# touche_server.net
KiCad netlist of a schematic drawn in EAGLE
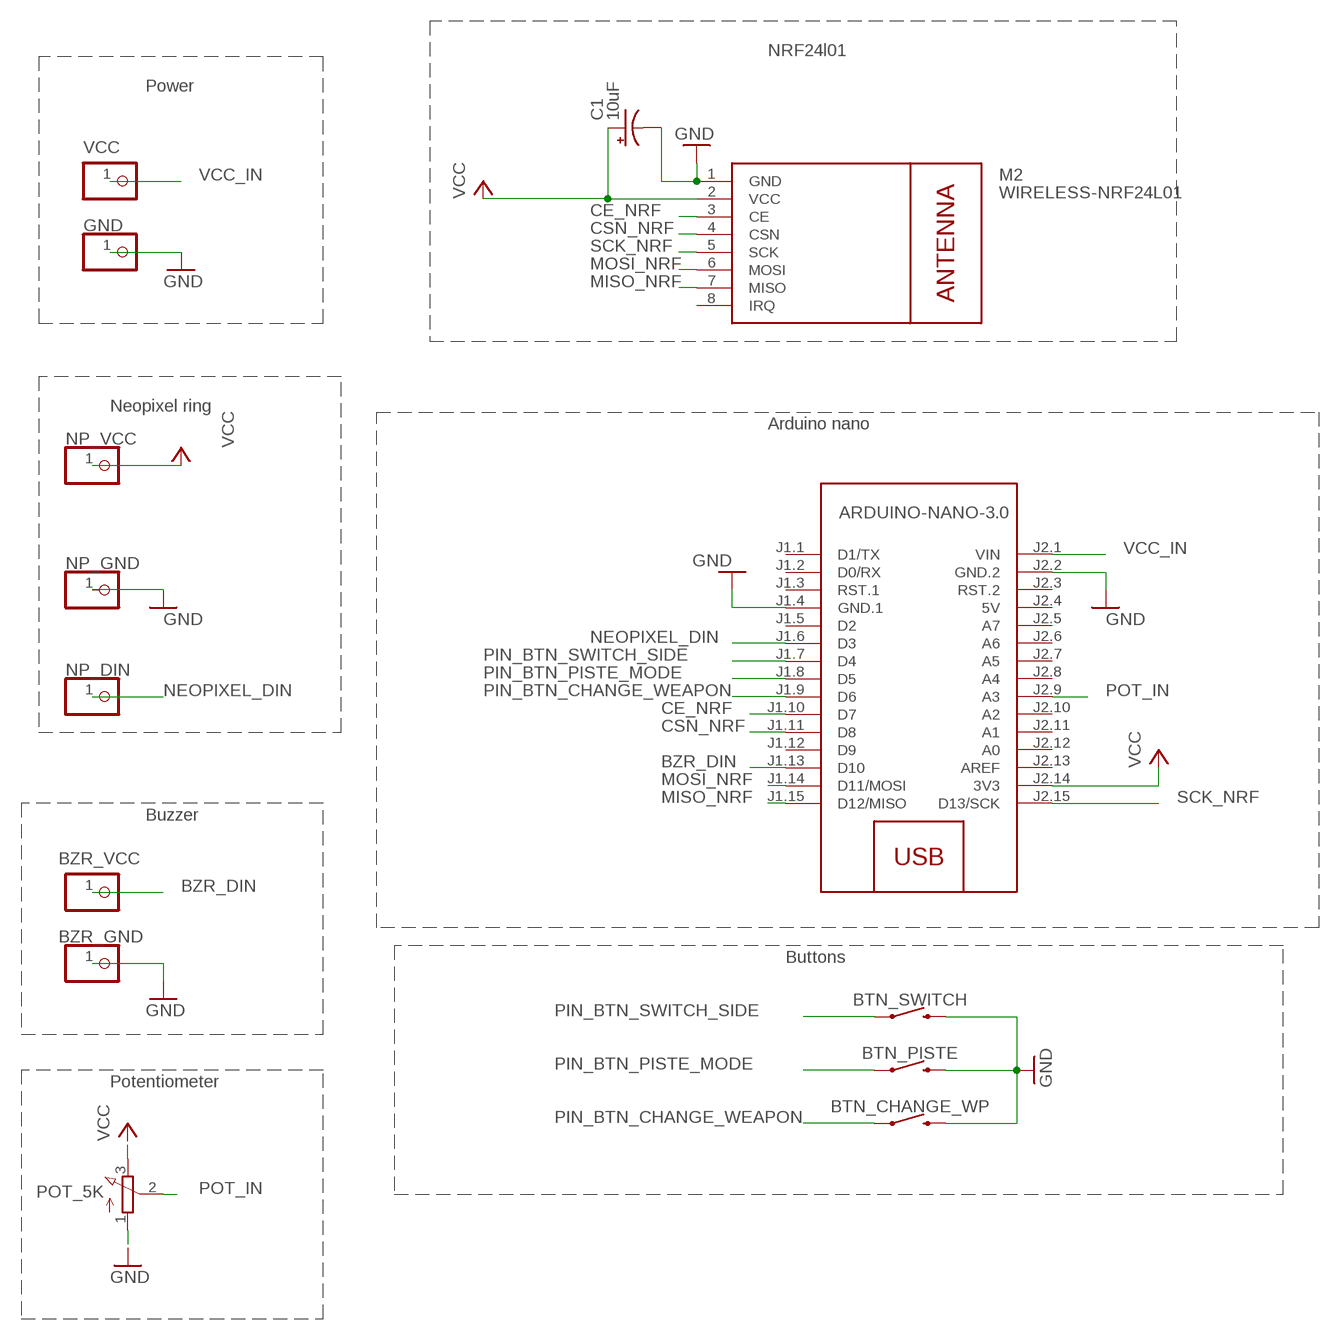
[diagram p0: schematic, sheet 1]

(export (version "E")
  (design (tool "Eeschema 10.0.6"))
  (components
    (comp (ref "BTN_CHANGE_WP")
      (value "MOMENTARY-SWITCH-SPST-PTH-RIGHT-ANGLE-KIT")
      (footprint "eagle-import:TACTILE_SWITCH_PTH_RIGHT_ANGLE_KIT")
      (libsource (lib "eagle-import") (part "MOMENTARY-SWITCH-SPST-PTH-RIGHT-ANGLE-KIT"))
    )
    (comp (ref "BTN_PISTE")
      (value "MOMENTARY-SWITCH-SPST-PTH-RIGHT-ANGLE-KIT")
      (footprint "eagle-import:TACTILE_SWITCH_PTH_RIGHT_ANGLE_KIT")
      (libsource (lib "eagle-import") (part "MOMENTARY-SWITCH-SPST-PTH-RIGHT-ANGLE-KIT"))
    )
    (comp (ref "BTN_SWITCH")
      (value "MOMENTARY-SWITCH-SPST-PTH-RIGHT-ANGLE-KIT")
      (footprint "eagle-import:TACTILE_SWITCH_PTH_RIGHT_ANGLE_KIT")
      (libsource (lib "eagle-import") (part "MOMENTARY-SWITCH-SPST-PTH-RIGHT-ANGLE-KIT"))
    )
    (comp (ref "BZR_GND")
      (value "BZR_GND")
      (footprint "eagle-import:1X01")
      (libsource (lib "eagle-import") (part "PINHD-1X1"))
    )
    (comp (ref "BZR_VCC")
      (value "BZR_VCC")
      (footprint "eagle-import:1X01")
      (libsource (lib "eagle-import") (part "PINHD-1X1"))
    )
    (comp (ref "C1")
      (value "10uF")
      (footprint "eagle-import:E2-5")
      (libsource (lib "eagle-import") (part "CPOL-USE2-5"))
    )
    (comp (ref "GND")
      (value "GND")
      (footprint "eagle-import:1X01")
      (libsource (lib "eagle-import") (part "PINHD-1X1"))
    )
    (comp (ref "M1")
      (value "ARDUINO-NANO-3.0")
      (footprint "eagle-import:ARDUINO-NANO-3.0")
      (libsource (lib "eagle-import") (part "ARDUINO-NANO-3.0"))
    )
    (comp (ref "M2")
      (value "WIRELESS-NRF24L01")
      (footprint "eagle-import:WIRELESS-NRF24L01")
      (libsource (lib "eagle-import") (part "WIRELESS-NRF24L01"))
    )
    (comp (ref "NP_DIN")
      (value "NP_DIN")
      (footprint "eagle-import:1X01")
      (libsource (lib "eagle-import") (part "PINHD-1X1"))
    )
    (comp (ref "NP_GND")
      (value "NP_GND")
      (footprint "eagle-import:1X01")
      (libsource (lib "eagle-import") (part "PINHD-1X1"))
    )
    (comp (ref "NP_VCC")
      (value "NP_VCC")
      (footprint "eagle-import:1X01")
      (libsource (lib "eagle-import") (part "PINHD-1X1"))
    )
    (comp (ref "POT_5K")
      (value "3RP/1610N")
      (footprint "eagle-import:3RP_1610N")
      (libsource (lib "eagle-import") (part "3RP/1610N"))
    )
    (comp (ref "VCC")
      (value "VCC")
      (footprint "eagle-import:1X01")
      (libsource (lib "eagle-import") (part "PINHD-1X1"))
    )
  )
  (nets
    (net (code "1") (name "/5V") (class "Default")
      (node (ref "M1") (pin "J2.4") (pinfunction "5V_J2.4") (pintype "power_in"))
    )
    (net (code "2") (name "/BZR_DIN") (class "Default")
      (node (ref "BZR_VCC") (pin "1") (pinfunction "1_1") (pintype "passive"))
      (node (ref "M1") (pin "J1.13") (pinfunction "D10_J1.13") (pintype "bidirectional"))
    )
    (net (code "3") (name "/CE_NRF") (class "Default")
      (node (ref "M1") (pin "J1.10") (pinfunction "D7_J1.10") (pintype "bidirectional"))
      (node (ref "M2") (pin "3") (pinfunction "CE_3") (pintype "bidirectional"))
    )
    (net (code "4") (name "/CSN_NRF") (class "Default")
      (node (ref "M1") (pin "J1.11") (pinfunction "D8_J1.11") (pintype "bidirectional"))
      (node (ref "M2") (pin "4") (pinfunction "CSN_4") (pintype "bidirectional"))
    )
    (net (code "5") (name "/MISO_NRF") (class "Default")
      (node (ref "M1") (pin "J1.15") (pinfunction "D12/MISO_J1.15") (pintype "bidirectional"))
      (node (ref "M2") (pin "7") (pinfunction "MISO_7") (pintype "bidirectional"))
    )
    (net (code "6") (name "/MOSI_NRF") (class "Default")
      (node (ref "M1") (pin "J1.14") (pinfunction "D11/MOSI_J1.14") (pintype "bidirectional"))
      (node (ref "M2") (pin "6") (pinfunction "MOSI_6") (pintype "bidirectional"))
    )
    (net (code "7") (name "/NEOPIXEL_DIN") (class "Default")
      (node (ref "M1") (pin "J1.6") (pinfunction "D3_J1.6") (pintype "bidirectional"))
      (node (ref "NP_DIN") (pin "1") (pinfunction "1_1") (pintype "passive"))
    )
    (net (code "8") (name "/PIN_BTN_CHANGE_WEAPON") (class "Default")
      (node (ref "BTN_CHANGE_WP") (pin "1") (pinfunction "1_1") (pintype "passive"))
      (node (ref "M1") (pin "J1.9") (pinfunction "D6_J1.9") (pintype "bidirectional"))
    )
    (net (code "9") (name "/PIN_BTN_PISTE_MODE") (class "Default")
      (node (ref "BTN_PISTE") (pin "1") (pinfunction "1_1") (pintype "passive"))
      (node (ref "M1") (pin "J1.8") (pinfunction "D5_J1.8") (pintype "bidirectional"))
    )
    (net (code "10") (name "/PIN_BTN_SWITCH_SIDE") (class "Default")
      (node (ref "BTN_SWITCH") (pin "1") (pinfunction "1_1") (pintype "passive"))
      (node (ref "M1") (pin "J1.7") (pinfunction "D4_J1.7") (pintype "bidirectional"))
    )
    (net (code "11") (name "/POT_IN") (class "Default")
      (node (ref "M1") (pin "J2.9") (pinfunction "A3_J2.9") (pintype "bidirectional"))
      (node (ref "POT_5K") (pin "2") (pinfunction "S_2") (pintype "passive"))
    )
    (net (code "12") (name "/SCK_NRF") (class "Default")
      (node (ref "M1") (pin "J2.15") (pinfunction "D13/SCK_J2.15") (pintype "bidirectional"))
      (node (ref "M2") (pin "5") (pinfunction "SCK_5") (pintype "bidirectional"))
    )
    (net (code "13") (name "/VCC_IN") (class "Default")
      (node (ref "M1") (pin "J2.1") (pinfunction "VIN_J2.1") (pintype "power_in"))
      (node (ref "VCC") (pin "1") (pinfunction "1_1") (pintype "passive"))
    )
    (net (code "14") (name "GND") (class "Default")
      (node (ref "BTN_CHANGE_WP") (pin "2") (pinfunction "2_2") (pintype "passive"))
      (node (ref "BTN_PISTE") (pin "2") (pinfunction "2_2") (pintype "passive"))
      (node (ref "BTN_SWITCH") (pin "2") (pinfunction "2_2") (pintype "passive"))
      (node (ref "BZR_GND") (pin "1") (pinfunction "1_1") (pintype "passive"))
      (node (ref "C1") (pin "-") (pinfunction "-_-") (pintype "passive"))
      (node (ref "GND") (pin "1") (pinfunction "1_1") (pintype "passive"))
      (node (ref "M1") (pin "J1.4") (pinfunction "GND.1_J1.4") (pintype "power_in"))
      (node (ref "M1") (pin "J2.2") (pinfunction "GND.2_J2.2") (pintype "power_in"))
      (node (ref "M2") (pin "1") (pinfunction "GND_1") (pintype "power_in"))
      (node (ref "NP_GND") (pin "1") (pinfunction "1_1") (pintype "passive"))
      (node (ref "POT_5K") (pin "1") (pinfunction "A_1") (pintype "passive"))
    )
    (net (code "15") (name "VCC") (class "Default")
      (node (ref "C1") (pin "+") (pinfunction "+_+") (pintype "passive"))
      (node (ref "M1") (pin "J2.14") (pinfunction "3V3_J2.14") (pintype "power_in"))
      (node (ref "M2") (pin "2") (pinfunction "VCC_2") (pintype "power_in"))
      (node (ref "NP_VCC") (pin "1") (pinfunction "1_1") (pintype "passive"))
      (node (ref "POT_5K") (pin "3") (pinfunction "E_3") (pintype "passive"))
    )
    (net (code "16") (name "unconnected-(M1-A0-PadJ2.12)") (class "Default")
      (node (ref "M1") (pin "J2.12") (pinfunction "A0_J2.12") (pintype "bidirectional"))
    )
    (net (code "17") (name "unconnected-(M1-A1-PadJ2.11)") (class "Default")
      (node (ref "M1") (pin "J2.11") (pinfunction "A1_J2.11") (pintype "bidirectional"))
    )
    (net (code "18") (name "unconnected-(M1-A2-PadJ2.10)") (class "Default")
      (node (ref "M1") (pin "J2.10") (pinfunction "A2_J2.10") (pintype "bidirectional"))
    )
    (net (code "19") (name "unconnected-(M1-A4-PadJ2.8)") (class "Default")
      (node (ref "M1") (pin "J2.8") (pinfunction "A4_J2.8") (pintype "bidirectional"))
    )
    (net (code "20") (name "unconnected-(M1-A5-PadJ2.7)") (class "Default")
      (node (ref "M1") (pin "J2.7") (pinfunction "A5_J2.7") (pintype "bidirectional"))
    )
    (net (code "21") (name "unconnected-(M1-A6-PadJ2.6)") (class "Default")
      (node (ref "M1") (pin "J2.6") (pinfunction "A6_J2.6") (pintype "bidirectional"))
    )
    (net (code "22") (name "unconnected-(M1-A7-PadJ2.5)") (class "Default")
      (node (ref "M1") (pin "J2.5") (pinfunction "A7_J2.5") (pintype "bidirectional"))
    )
    (net (code "23") (name "unconnected-(M1-AREF-PadJ2.13)") (class "Default")
      (node (ref "M1") (pin "J2.13") (pinfunction "AREF_J2.13") (pintype "bidirectional"))
    )
    (net (code "24") (name "unconnected-(M1-D0{slash}RX-PadJ1.2)") (class "Default")
      (node (ref "M1") (pin "J1.2") (pinfunction "D0/RX_J1.2") (pintype "bidirectional"))
    )
    (net (code "25") (name "unconnected-(M1-D1{slash}TX-PadJ1.1)") (class "Default")
      (node (ref "M1") (pin "J1.1") (pinfunction "D1/TX_J1.1") (pintype "bidirectional"))
    )
    (net (code "26") (name "unconnected-(M1-D2-PadJ1.5)") (class "Default")
      (node (ref "M1") (pin "J1.5") (pinfunction "D2_J1.5") (pintype "bidirectional"))
    )
    (net (code "27") (name "unconnected-(M1-D9-PadJ1.12)") (class "Default")
      (node (ref "M1") (pin "J1.12") (pinfunction "D9_J1.12") (pintype "bidirectional"))
    )
    (net (code "28") (name "unconnected-(M1-RST.1-PadJ1.3)") (class "Default")
      (node (ref "M1") (pin "J1.3") (pinfunction "RST.1_J1.3") (pintype "bidirectional"))
    )
    (net (code "29") (name "unconnected-(M1-RST.2-PadJ2.3)") (class "Default")
      (node (ref "M1") (pin "J2.3") (pinfunction "RST.2_J2.3") (pintype "bidirectional"))
    )
    (net (code "30") (name "unconnected-(M2-IRQ-Pad8)") (class "Default")
      (node (ref "M2") (pin "8") (pinfunction "IRQ_8") (pintype "bidirectional"))
    )
  )
)
